# Bus_master_Sheet.net
KiCad netlist of a schematic drawn in Altium Designer
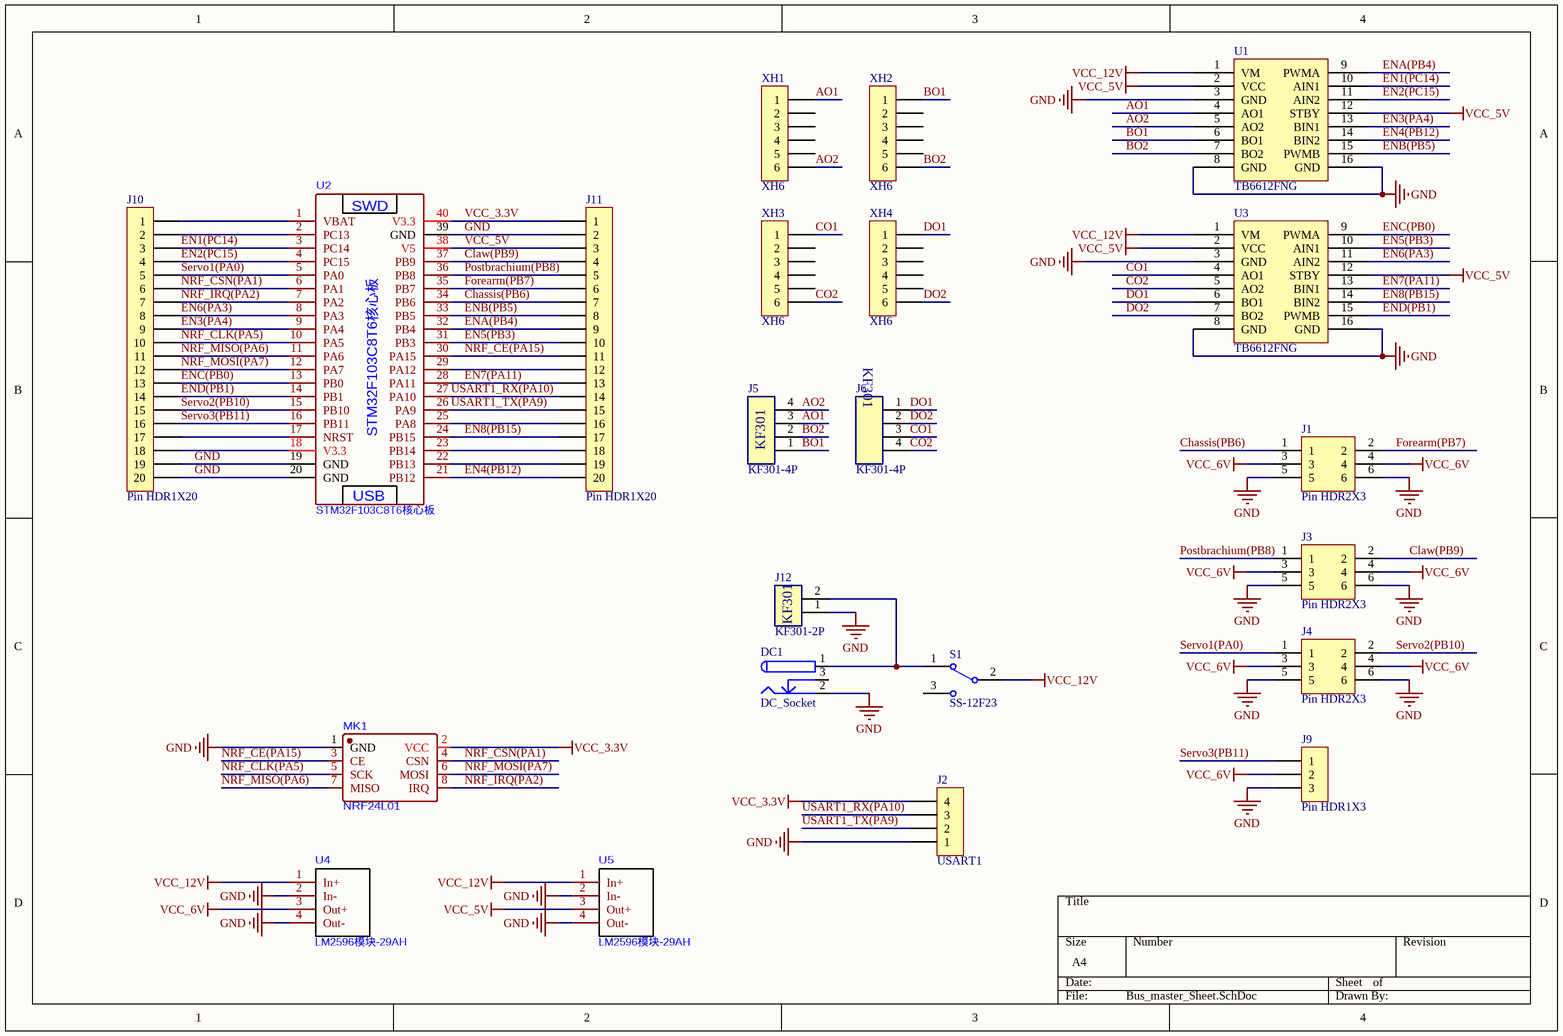
[diagram p0: Bus_master_Sheet.SchDoc]

(export (version "E")
  (design (tool "Eeschema 10.0.6"))
  (components
    (comp (ref "DC1") (value "DC_Socket") (footprint "DC-005") (libsource (lib "电源插座") (part "DC_Socket")))
    (comp (ref "J1")
      (value "Pin HDR2X3")
      (footprint "Pin HDR2X3/2.54mm-S")
      (libsource (lib "排针") (part "Pin HDR2X3"))
    )
    (comp (ref "J2")
      (value "USART1")
      (footprint "Pin HDR1X4/2.54mm-W")
      (libsource (lib "排针") (part "Pin HDR1X4"))
    )
    (comp (ref "J3")
      (value "Pin HDR2X3")
      (footprint "Pin HDR2X3/2.54mm-S")
      (libsource (lib "排针") (part "Pin HDR2X3"))
    )
    (comp (ref "J4")
      (value "Pin HDR2X3")
      (footprint "Pin HDR2X3/2.54mm-S")
      (libsource (lib "排针") (part "Pin HDR2X3"))
    )
    (comp (ref "J5")
      (value "KF301-4P")
      (footprint "KF301-5.0-4P")
      (libsource (lib "KF301") (part "KF301-4P"))
    )
    (comp (ref "J6") (value "KF301-4P") (footprint "KF301-5.0-4P") (libsource (lib "") (part "KF301-4P_1")))
    (comp (ref "J9")
      (value "Pin HDR1X3")
      (footprint "Pin HDR1X3/2.54mm-S")
      (libsource (lib "排针") (part "Pin HDR1X3"))
    )
    (comp (ref "J10")
      (value "Pin HDR1X20")
      (footprint "Pin HDR1X20/2.54mm-S")
      (libsource (lib "排针") (part "Pin HDR1X20"))
    )
    (comp (ref "J11")
      (value "Pin HDR1X20")
      (footprint "Pin HDR1X20/2.54mm-S")
      (libsource (lib "") (part "Pin HDR1X20_1"))
    )
    (comp (ref "J12")
      (value "KF301-2P")
      (footprint "KF301-5.0-2P")
      (libsource (lib "KF301") (part "KF301-2P"))
    )
    (comp (ref "MK1")
      (value "NRF24L01")
      (footprint "WIRELM-SMD_NRF24L01")
      (libsource (lib "zy lib") (part "NRF24L01"))
    )
    (comp (ref "S1") (value "SS-12F23") (footprint "SS-12F23") (libsource (lib "电源开关") (part "SS-12F23")))
    (comp (ref "U1") (value "TB6612FNG") (footprint "TB6612") (libsource (lib "zy lib") (part "TB6612FNG")))
    (comp (ref "U2")
      (value "STM32F103C8T6核心板")
      (footprint "STM32F103C8T6")
      (libsource (lib "zy lib") (part "STM32F103C8T6核心板"))
    )
    (comp (ref "U3") (value "TB6612FNG") (footprint "TB6612") (libsource (lib "zy lib") (part "TB6612FNG")))
    (comp (ref "U4")
      (value "LM2596模块-29AH")
      (footprint "LM2596")
      (libsource (lib "zy lib") (part "LM2596模块-29AH"))
    )
    (comp (ref "U5")
      (value "LM2596模块-29AH")
      (footprint "LM2596")
      (libsource (lib "zy lib") (part "LM2596模块-29AH"))
    )
    (comp (ref "XH1") (value "XH6") (footprint "XH6/2.54mm/90") (libsource (lib "XH，VH") (part "XH6")))
    (comp (ref "XH2") (value "XH6") (footprint "XH6/2.54mm/90") (libsource (lib "XH，VH") (part "XH6")))
    (comp (ref "XH3") (value "XH6") (footprint "XH6/2.54mm/90") (libsource (lib "XH，VH") (part "XH6")))
    (comp (ref "XH4") (value "XH6") (footprint "XH6/2.54mm/90") (libsource (lib "XH，VH") (part "XH6")))
  )
  (nets
    (net (code "1") (name "/AO1") (class "Default")
      (node (ref "J5") (pin "3") (pinfunction "3_3") (pintype "passive"))
      (node (ref "U1") (pin "4") (pinfunction "AO1_4") (pintype "passive"))
      (node (ref "XH1") (pin "1") (pinfunction "1_1") (pintype "passive"))
    )
    (net (code "2") (name "/AO2") (class "Default")
      (node (ref "J5") (pin "4") (pinfunction "4_4") (pintype "passive"))
      (node (ref "U1") (pin "5") (pinfunction "AO2_5") (pintype "passive"))
      (node (ref "XH1") (pin "6") (pinfunction "6_6") (pintype "passive"))
    )
    (net (code "3") (name "/BO1") (class "Default")
      (node (ref "J5") (pin "1") (pinfunction "1_1") (pintype "passive"))
      (node (ref "U1") (pin "6") (pinfunction "BO1_6") (pintype "passive"))
      (node (ref "XH2") (pin "1") (pinfunction "1_1") (pintype "passive"))
    )
    (net (code "4") (name "/BO2") (class "Default")
      (node (ref "J5") (pin "2") (pinfunction "2_2") (pintype "passive"))
      (node (ref "U1") (pin "7") (pinfunction "BO2_7") (pintype "passive"))
      (node (ref "XH2") (pin "6") (pinfunction "6_6") (pintype "passive"))
    )
    (net (code "5") (name "/CO1") (class "Default")
      (node (ref "J6") (pin "3") (pinfunction "3_3") (pintype "passive"))
      (node (ref "U3") (pin "4") (pinfunction "AO1_4") (pintype "passive"))
      (node (ref "XH3") (pin "1") (pinfunction "1_1") (pintype "passive"))
    )
    (net (code "6") (name "/CO2") (class "Default")
      (node (ref "J6") (pin "4") (pinfunction "4_4") (pintype "passive"))
      (node (ref "U3") (pin "5") (pinfunction "AO2_5") (pintype "passive"))
      (node (ref "XH3") (pin "6") (pinfunction "6_6") (pintype "passive"))
    )
    (net (code "7") (name "/Chassis(PB6)") (class "Default")
      (node (ref "J1") (pin "1") (pinfunction "1_1") (pintype "passive"))
      (node (ref "J11") (pin "7") (pinfunction "7_7") (pintype "passive"))
      (node (ref "U2") (pin "34") (pinfunction "PB6_34") (pintype "passive"))
    )
    (net (code "8") (name "/Claw(PB9)") (class "Default")
      (node (ref "J11") (pin "4") (pinfunction "4_4") (pintype "passive"))
      (node (ref "J3") (pin "2") (pinfunction "2_2") (pintype "passive"))
      (node (ref "U2") (pin "37") (pinfunction "PB9_37") (pintype "passive"))
    )
    (net (code "9") (name "/DO1") (class "Default")
      (node (ref "J6") (pin "1") (pinfunction "1_1") (pintype "passive"))
      (node (ref "U3") (pin "6") (pinfunction "BO1_6") (pintype "passive"))
      (node (ref "XH4") (pin "1") (pinfunction "1_1") (pintype "passive"))
    )
    (net (code "10") (name "/DO2") (class "Default")
      (node (ref "J6") (pin "2") (pinfunction "2_2") (pintype "passive"))
      (node (ref "U3") (pin "7") (pinfunction "BO2_7") (pintype "passive"))
      (node (ref "XH4") (pin "6") (pinfunction "6_6") (pintype "passive"))
    )
    (net (code "11") (name "/EN1(PC14)") (class "Default")
      (node (ref "J10") (pin "3") (pinfunction "3_3") (pintype "passive"))
      (node (ref "U1") (pin "10") (pinfunction "AIN1_10") (pintype "passive"))
      (node (ref "U2") (pin "3") (pinfunction "PC14_3") (pintype "passive"))
    )
    (net (code "12") (name "/EN2(PC15)") (class "Default")
      (node (ref "J10") (pin "4") (pinfunction "4_4") (pintype "passive"))
      (node (ref "U1") (pin "11") (pinfunction "AIN2_11") (pintype "passive"))
      (node (ref "U2") (pin "4") (pinfunction "PC15_4") (pintype "passive"))
    )
    (net (code "13") (name "/EN3(PA4)") (class "Default")
      (node (ref "J10") (pin "9") (pinfunction "9_9") (pintype "passive"))
      (node (ref "U1") (pin "13") (pinfunction "BIN1_13") (pintype "passive"))
      (node (ref "U2") (pin "9") (pinfunction "PA4_9") (pintype "passive"))
    )
    (net (code "14") (name "/EN4(PB12)") (class "Default")
      (node (ref "J11") (pin "20") (pinfunction "20_20") (pintype "passive"))
      (node (ref "U1") (pin "14") (pinfunction "BIN2_14") (pintype "passive"))
      (node (ref "U2") (pin "21") (pinfunction "PB12_21") (pintype "passive"))
    )
    (net (code "15") (name "/EN5(PB3)") (class "Default")
      (node (ref "J11") (pin "10") (pinfunction "10_10") (pintype "passive"))
      (node (ref "U2") (pin "31") (pinfunction "PB3_31") (pintype "passive"))
      (node (ref "U3") (pin "10") (pinfunction "AIN1_10") (pintype "passive"))
    )
    (net (code "16") (name "/EN6(PA3)") (class "Default")
      (node (ref "J10") (pin "8") (pinfunction "8_8") (pintype "passive"))
      (node (ref "U2") (pin "8") (pinfunction "PA3_8") (pintype "passive"))
      (node (ref "U3") (pin "11") (pinfunction "AIN2_11") (pintype "passive"))
    )
    (net (code "17") (name "/EN7(PA11)") (class "Default")
      (node (ref "J11") (pin "13") (pinfunction "13_13") (pintype "passive"))
      (node (ref "U2") (pin "28") (pinfunction "PA11_28") (pintype "passive"))
      (node (ref "U3") (pin "13") (pinfunction "BIN1_13") (pintype "passive"))
    )
    (net (code "18") (name "/EN8(PB15)") (class "Default")
      (node (ref "J11") (pin "17") (pinfunction "17_17") (pintype "passive"))
      (node (ref "U2") (pin "24") (pinfunction "PB15_24") (pintype "passive"))
      (node (ref "U3") (pin "14") (pinfunction "BIN2_14") (pintype "passive"))
    )
    (net (code "19") (name "/ENA(PB4)") (class "Default")
      (node (ref "J11") (pin "9") (pinfunction "9_9") (pintype "passive"))
      (node (ref "U1") (pin "9") (pinfunction "PWMA_9") (pintype "passive"))
      (node (ref "U2") (pin "32") (pinfunction "PB4_32") (pintype "passive"))
    )
    (net (code "20") (name "/ENB(PB5)") (class "Default")
      (node (ref "J11") (pin "8") (pinfunction "8_8") (pintype "passive"))
      (node (ref "U1") (pin "15") (pinfunction "PWMB_15") (pintype "passive"))
      (node (ref "U2") (pin "33") (pinfunction "PB5_33") (pintype "passive"))
    )
    (net (code "21") (name "/ENC(PB0)") (class "Default")
      (node (ref "J10") (pin "13") (pinfunction "13_13") (pintype "passive"))
      (node (ref "U2") (pin "13") (pinfunction "PB0_13") (pintype "passive"))
      (node (ref "U3") (pin "9") (pinfunction "PWMA_9") (pintype "passive"))
    )
    (net (code "22") (name "/END(PB1)") (class "Default")
      (node (ref "J10") (pin "14") (pinfunction "14_14") (pintype "passive"))
      (node (ref "U2") (pin "14") (pinfunction "PB1_14") (pintype "passive"))
      (node (ref "U3") (pin "15") (pinfunction "PWMB_15") (pintype "passive"))
    )
    (net (code "23") (name "/Forearm(PB7)") (class "Default")
      (node (ref "J1") (pin "2") (pinfunction "2_2") (pintype "passive"))
      (node (ref "J11") (pin "6") (pinfunction "6_6") (pintype "passive"))
      (node (ref "U2") (pin "35") (pinfunction "PB7_35") (pintype "passive"))
    )
    (net (code "24") (name "/NRF_CE(PA15)") (class "Default")
      (node (ref "J11") (pin "11") (pinfunction "11_11") (pintype "passive"))
      (node (ref "MK1") (pin "3") (pinfunction "CE_3") (pintype "passive"))
      (node (ref "U2") (pin "30") (pinfunction "PA15_30") (pintype "passive"))
    )
    (net (code "25") (name "/NRF_CLK(PA5)") (class "Default")
      (node (ref "J10") (pin "10") (pinfunction "10_10") (pintype "passive"))
      (node (ref "MK1") (pin "5") (pinfunction "SCK_5") (pintype "passive"))
      (node (ref "U2") (pin "10") (pinfunction "PA5_10") (pintype "passive"))
    )
    (net (code "26") (name "/NRF_CSN(PA1)") (class "Default")
      (node (ref "J10") (pin "6") (pinfunction "6_6") (pintype "passive"))
      (node (ref "MK1") (pin "4") (pinfunction "CSN_4") (pintype "passive"))
      (node (ref "U2") (pin "6") (pinfunction "PA1_6") (pintype "passive"))
    )
    (net (code "27") (name "/NRF_IRQ(PA2)") (class "Default")
      (node (ref "J10") (pin "7") (pinfunction "7_7") (pintype "passive"))
      (node (ref "MK1") (pin "8") (pinfunction "IRQ_8") (pintype "passive"))
      (node (ref "U2") (pin "7") (pinfunction "PA2_7") (pintype "passive"))
    )
    (net (code "28") (name "/NRF_MISO(PA6)") (class "Default")
      (node (ref "J10") (pin "11") (pinfunction "11_11") (pintype "passive"))
      (node (ref "MK1") (pin "7") (pinfunction "MISO_7") (pintype "passive"))
      (node (ref "U2") (pin "11") (pinfunction "PA6_11") (pintype "passive"))
    )
    (net (code "29") (name "/NRF_MOSI(PA7)") (class "Default")
      (node (ref "J10") (pin "12") (pinfunction "12_12") (pintype "passive"))
      (node (ref "MK1") (pin "6") (pinfunction "MOSI_6") (pintype "passive"))
      (node (ref "U2") (pin "12") (pinfunction "PA7_12") (pintype "passive"))
    )
    (net (code "30") (name "/Postbrachium(PB8)") (class "Default")
      (node (ref "J11") (pin "5") (pinfunction "5_5") (pintype "passive"))
      (node (ref "J3") (pin "1") (pinfunction "1_1") (pintype "passive"))
      (node (ref "U2") (pin "36") (pinfunction "PB8_36") (pintype "passive"))
    )
    (net (code "31") (name "/Servo1(PA0)") (class "Default")
      (node (ref "J10") (pin "5") (pinfunction "5_5") (pintype "passive"))
      (node (ref "J4") (pin "1") (pinfunction "1_1") (pintype "passive"))
      (node (ref "U2") (pin "5") (pinfunction "PA0_5") (pintype "passive"))
    )
    (net (code "32") (name "/Servo2(PB10)") (class "Default")
      (node (ref "J10") (pin "15") (pinfunction "15_15") (pintype "passive"))
      (node (ref "J4") (pin "2") (pinfunction "2_2") (pintype "passive"))
      (node (ref "U2") (pin "15") (pinfunction "PB10_15") (pintype "passive"))
    )
    (net (code "33") (name "/Servo3(PB11)") (class "Default")
      (node (ref "J10") (pin "16") (pinfunction "16_16") (pintype "passive"))
      (node (ref "J9") (pin "1") (pinfunction "1_1") (pintype "passive"))
      (node (ref "U2") (pin "16") (pinfunction "PB11_16") (pintype "passive"))
    )
    (net (code "34") (name "/USART1_RX(PA10)") (class "Default")
      (node (ref "J11") (pin "14") (pinfunction "14_14") (pintype "passive"))
      (node (ref "J2") (pin "3") (pinfunction "3_3") (pintype "passive"))
      (node (ref "U2") (pin "27") (pinfunction "PA10_27") (pintype "passive"))
    )
    (net (code "35") (name "/USART1_TX(PA9)") (class "Default")
      (node (ref "J11") (pin "15") (pinfunction "15_15") (pintype "passive"))
      (node (ref "J2") (pin "2") (pinfunction "2_2") (pintype "passive"))
      (node (ref "U2") (pin "26") (pinfunction "PA9_26") (pintype "passive"))
    )
    (net (code "36") (name "GND") (class "Default")
      (node (ref "DC1") (pin "2") (pinfunction "2_2") (pintype "power_in"))
      (node (ref "J1") (pin "5") (pinfunction "5_5") (pintype "passive"))
      (node (ref "J1") (pin "6") (pinfunction "6_6") (pintype "passive"))
      (node (ref "J10") (pin "19") (pinfunction "19_19") (pintype "passive"))
      (node (ref "J10") (pin "20") (pinfunction "20_20") (pintype "passive"))
      (node (ref "J11") (pin "2") (pinfunction "2_2") (pintype "passive"))
      (node (ref "J12") (pin "1") (pinfunction "1_1") (pintype "passive"))
      (node (ref "J2") (pin "1") (pinfunction "1_1") (pintype "passive"))
      (node (ref "J3") (pin "5") (pinfunction "5_5") (pintype "passive"))
      (node (ref "J3") (pin "6") (pinfunction "6_6") (pintype "passive"))
      (node (ref "J4") (pin "5") (pinfunction "5_5") (pintype "passive"))
      (node (ref "J4") (pin "6") (pinfunction "6_6") (pintype "passive"))
      (node (ref "J9") (pin "3") (pinfunction "3_3") (pintype "passive"))
      (node (ref "MK1") (pin "1") (pinfunction "GND_1") (pintype "passive"))
      (node (ref "U1") (pin "16") (pinfunction "GND_16") (pintype "passive"))
      (node (ref "U1") (pin "3") (pinfunction "GND_3") (pintype "passive"))
      (node (ref "U1") (pin "8") (pinfunction "GND_8") (pintype "passive"))
      (node (ref "U2") (pin "19") (pinfunction "GND_19") (pintype "passive"))
      (node (ref "U2") (pin "20") (pinfunction "GND_20") (pintype "passive"))
      (node (ref "U2") (pin "39") (pinfunction "GND_39") (pintype "passive"))
      (node (ref "U3") (pin "16") (pinfunction "GND_16") (pintype "passive"))
      (node (ref "U3") (pin "3") (pinfunction "GND_3") (pintype "passive"))
      (node (ref "U3") (pin "8") (pinfunction "GND_8") (pintype "passive"))
      (node (ref "U4") (pin "2") (pinfunction "In-_2") (pintype "passive"))
      (node (ref "U4") (pin "4") (pinfunction "Out-_4") (pintype "passive"))
      (node (ref "U5") (pin "2") (pinfunction "In-_2") (pintype "passive"))
      (node (ref "U5") (pin "4") (pinfunction "Out-_4") (pintype "passive"))
    )
    (net (code "37") (name "Net-(DC1-Pad1)") (class "Default")
      (node (ref "DC1") (pin "1") (pinfunction "1_1") (pintype "power_in"))
      (node (ref "J12") (pin "2") (pinfunction "2_2") (pintype "passive"))
      (node (ref "S1") (pin "1") (pinfunction "1_1") (pintype "passive"))
    )
    (net (code "38") (name "Net-(J10-Pad18)") (class "Default")
      (node (ref "J10") (pin "18") (pinfunction "18_18") (pintype "passive"))
      (node (ref "U2") (pin "18") (pinfunction "V3.3_18") (pintype "passive"))
    )
    (net (code "39") (name "Net-(U2-NRST)") (class "Default")
      (node (ref "J10") (pin "17") (pinfunction "17_17") (pintype "passive"))
      (node (ref "U2") (pin "17") (pinfunction "NRST_17") (pintype "passive"))
    )
    (net (code "40") (name "Net-(U2-PA8)") (class "Default")
      (node (ref "J11") (pin "16") (pinfunction "16_16") (pintype "passive"))
      (node (ref "U2") (pin "25") (pinfunction "PA8_25") (pintype "passive"))
    )
    (net (code "41") (name "Net-(U2-PA12)") (class "Default")
      (node (ref "J11") (pin "12") (pinfunction "12_12") (pintype "passive"))
      (node (ref "U2") (pin "29") (pinfunction "PA12_29") (pintype "passive"))
    )
    (net (code "42") (name "Net-(U2-PB13)") (class "Default")
      (node (ref "J11") (pin "19") (pinfunction "19_19") (pintype "passive"))
      (node (ref "U2") (pin "22") (pinfunction "PB13_22") (pintype "passive"))
    )
    (net (code "43") (name "Net-(U2-PB14)") (class "Default")
      (node (ref "J11") (pin "18") (pinfunction "18_18") (pintype "passive"))
      (node (ref "U2") (pin "23") (pinfunction "PB14_23") (pintype "passive"))
    )
    (net (code "44") (name "Net-(U2-PC13)") (class "Default")
      (node (ref "J10") (pin "2") (pinfunction "2_2") (pintype "passive"))
      (node (ref "U2") (pin "2") (pinfunction "PC13_2") (pintype "passive"))
    )
    (net (code "45") (name "Net-(U2-VBAT)") (class "Default")
      (node (ref "J10") (pin "1") (pinfunction "1_1") (pintype "passive"))
      (node (ref "U2") (pin "1") (pinfunction "VBAT_1") (pintype "passive"))
    )
    (net (code "46") (name "VCC_3.3V") (class "Default")
      (node (ref "J11") (pin "1") (pinfunction "1_1") (pintype "passive"))
      (node (ref "J2") (pin "4") (pinfunction "4_4") (pintype "passive"))
      (node (ref "MK1") (pin "2") (pinfunction "VCC_2") (pintype "passive"))
      (node (ref "U2") (pin "40") (pinfunction "V3.3_40") (pintype "passive"))
    )
    (net (code "47") (name "VCC_5V") (class "Default")
      (node (ref "J11") (pin "3") (pinfunction "3_3") (pintype "passive"))
      (node (ref "U1") (pin "12") (pinfunction "STBY_12") (pintype "passive"))
      (node (ref "U1") (pin "2") (pinfunction "VCC_2") (pintype "passive"))
      (node (ref "U2") (pin "38") (pinfunction "V5_38") (pintype "passive"))
      (node (ref "U3") (pin "12") (pinfunction "STBY_12") (pintype "passive"))
      (node (ref "U3") (pin "2") (pinfunction "VCC_2") (pintype "passive"))
      (node (ref "U5") (pin "3") (pinfunction "Out+_3") (pintype "passive"))
    )
    (net (code "48") (name "VCC_6V") (class "Default")
      (node (ref "J1") (pin "3") (pinfunction "3_3") (pintype "passive"))
      (node (ref "J1") (pin "4") (pinfunction "4_4") (pintype "passive"))
      (node (ref "J3") (pin "3") (pinfunction "3_3") (pintype "passive"))
      (node (ref "J3") (pin "4") (pinfunction "4_4") (pintype "passive"))
      (node (ref "J4") (pin "3") (pinfunction "3_3") (pintype "passive"))
      (node (ref "J4") (pin "4") (pinfunction "4_4") (pintype "passive"))
      (node (ref "J9") (pin "2") (pinfunction "2_2") (pintype "passive"))
      (node (ref "U4") (pin "3") (pinfunction "Out+_3") (pintype "passive"))
    )
    (net (code "49") (name "VCC_12V") (class "Default")
      (node (ref "S1") (pin "2") (pinfunction "2_2") (pintype "passive"))
      (node (ref "U1") (pin "1") (pinfunction "VM_1") (pintype "passive"))
      (node (ref "U3") (pin "1") (pinfunction "VM_1") (pintype "passive"))
      (node (ref "U4") (pin "1") (pinfunction "In+_1") (pintype "passive"))
      (node (ref "U5") (pin "1") (pinfunction "In+_1") (pintype "passive"))
    )
    (net (code "50") (name "unconnected-(DC1-Pad3)") (class "Default")
      (node (ref "DC1") (pin "3") (pinfunction "3_3") (pintype "power_in"))
    )
    (net (code "51") (name "unconnected-(S1-Pad3)") (class "Default")
      (node (ref "S1") (pin "3") (pinfunction "3_3") (pintype "passive"))
    )
    (net (code "52") (name "unconnected-(XH1-Pad2)") (class "Default")
      (node (ref "XH1") (pin "2") (pinfunction "2_2") (pintype "passive"))
    )
    (net (code "53") (name "unconnected-(XH1-Pad3)") (class "Default")
      (node (ref "XH1") (pin "3") (pinfunction "3_3") (pintype "passive"))
    )
    (net (code "54") (name "unconnected-(XH1-Pad4)") (class "Default")
      (node (ref "XH1") (pin "4") (pinfunction "4_4") (pintype "passive"))
    )
    (net (code "55") (name "unconnected-(XH1-Pad5)") (class "Default")
      (node (ref "XH1") (pin "5") (pinfunction "5_5") (pintype "passive"))
    )
    (net (code "56") (name "unconnected-(XH2-Pad2)") (class "Default")
      (node (ref "XH2") (pin "2") (pinfunction "2_2") (pintype "passive"))
    )
    (net (code "57") (name "unconnected-(XH2-Pad3)") (class "Default")
      (node (ref "XH2") (pin "3") (pinfunction "3_3") (pintype "passive"))
    )
    (net (code "58") (name "unconnected-(XH2-Pad4)") (class "Default")
      (node (ref "XH2") (pin "4") (pinfunction "4_4") (pintype "passive"))
    )
    (net (code "59") (name "unconnected-(XH2-Pad5)") (class "Default")
      (node (ref "XH2") (pin "5") (pinfunction "5_5") (pintype "passive"))
    )
    (net (code "60") (name "unconnected-(XH3-Pad2)") (class "Default")
      (node (ref "XH3") (pin "2") (pinfunction "2_2") (pintype "passive"))
    )
    (net (code "61") (name "unconnected-(XH3-Pad3)") (class "Default")
      (node (ref "XH3") (pin "3") (pinfunction "3_3") (pintype "passive"))
    )
    (net (code "62") (name "unconnected-(XH3-Pad4)") (class "Default")
      (node (ref "XH3") (pin "4") (pinfunction "4_4") (pintype "passive"))
    )
    (net (code "63") (name "unconnected-(XH3-Pad5)") (class "Default")
      (node (ref "XH3") (pin "5") (pinfunction "5_5") (pintype "passive"))
    )
    (net (code "64") (name "unconnected-(XH4-Pad2)") (class "Default")
      (node (ref "XH4") (pin "2") (pinfunction "2_2") (pintype "passive"))
    )
    (net (code "65") (name "unconnected-(XH4-Pad3)") (class "Default")
      (node (ref "XH4") (pin "3") (pinfunction "3_3") (pintype "passive"))
    )
    (net (code "66") (name "unconnected-(XH4-Pad4)") (class "Default")
      (node (ref "XH4") (pin "4") (pinfunction "4_4") (pintype "passive"))
    )
    (net (code "67") (name "unconnected-(XH4-Pad5)") (class "Default")
      (node (ref "XH4") (pin "5") (pinfunction "5_5") (pintype "passive"))
    )
  )
)
